# schematic.net
KiCad netlist of a schematic drawn in EasyEDA
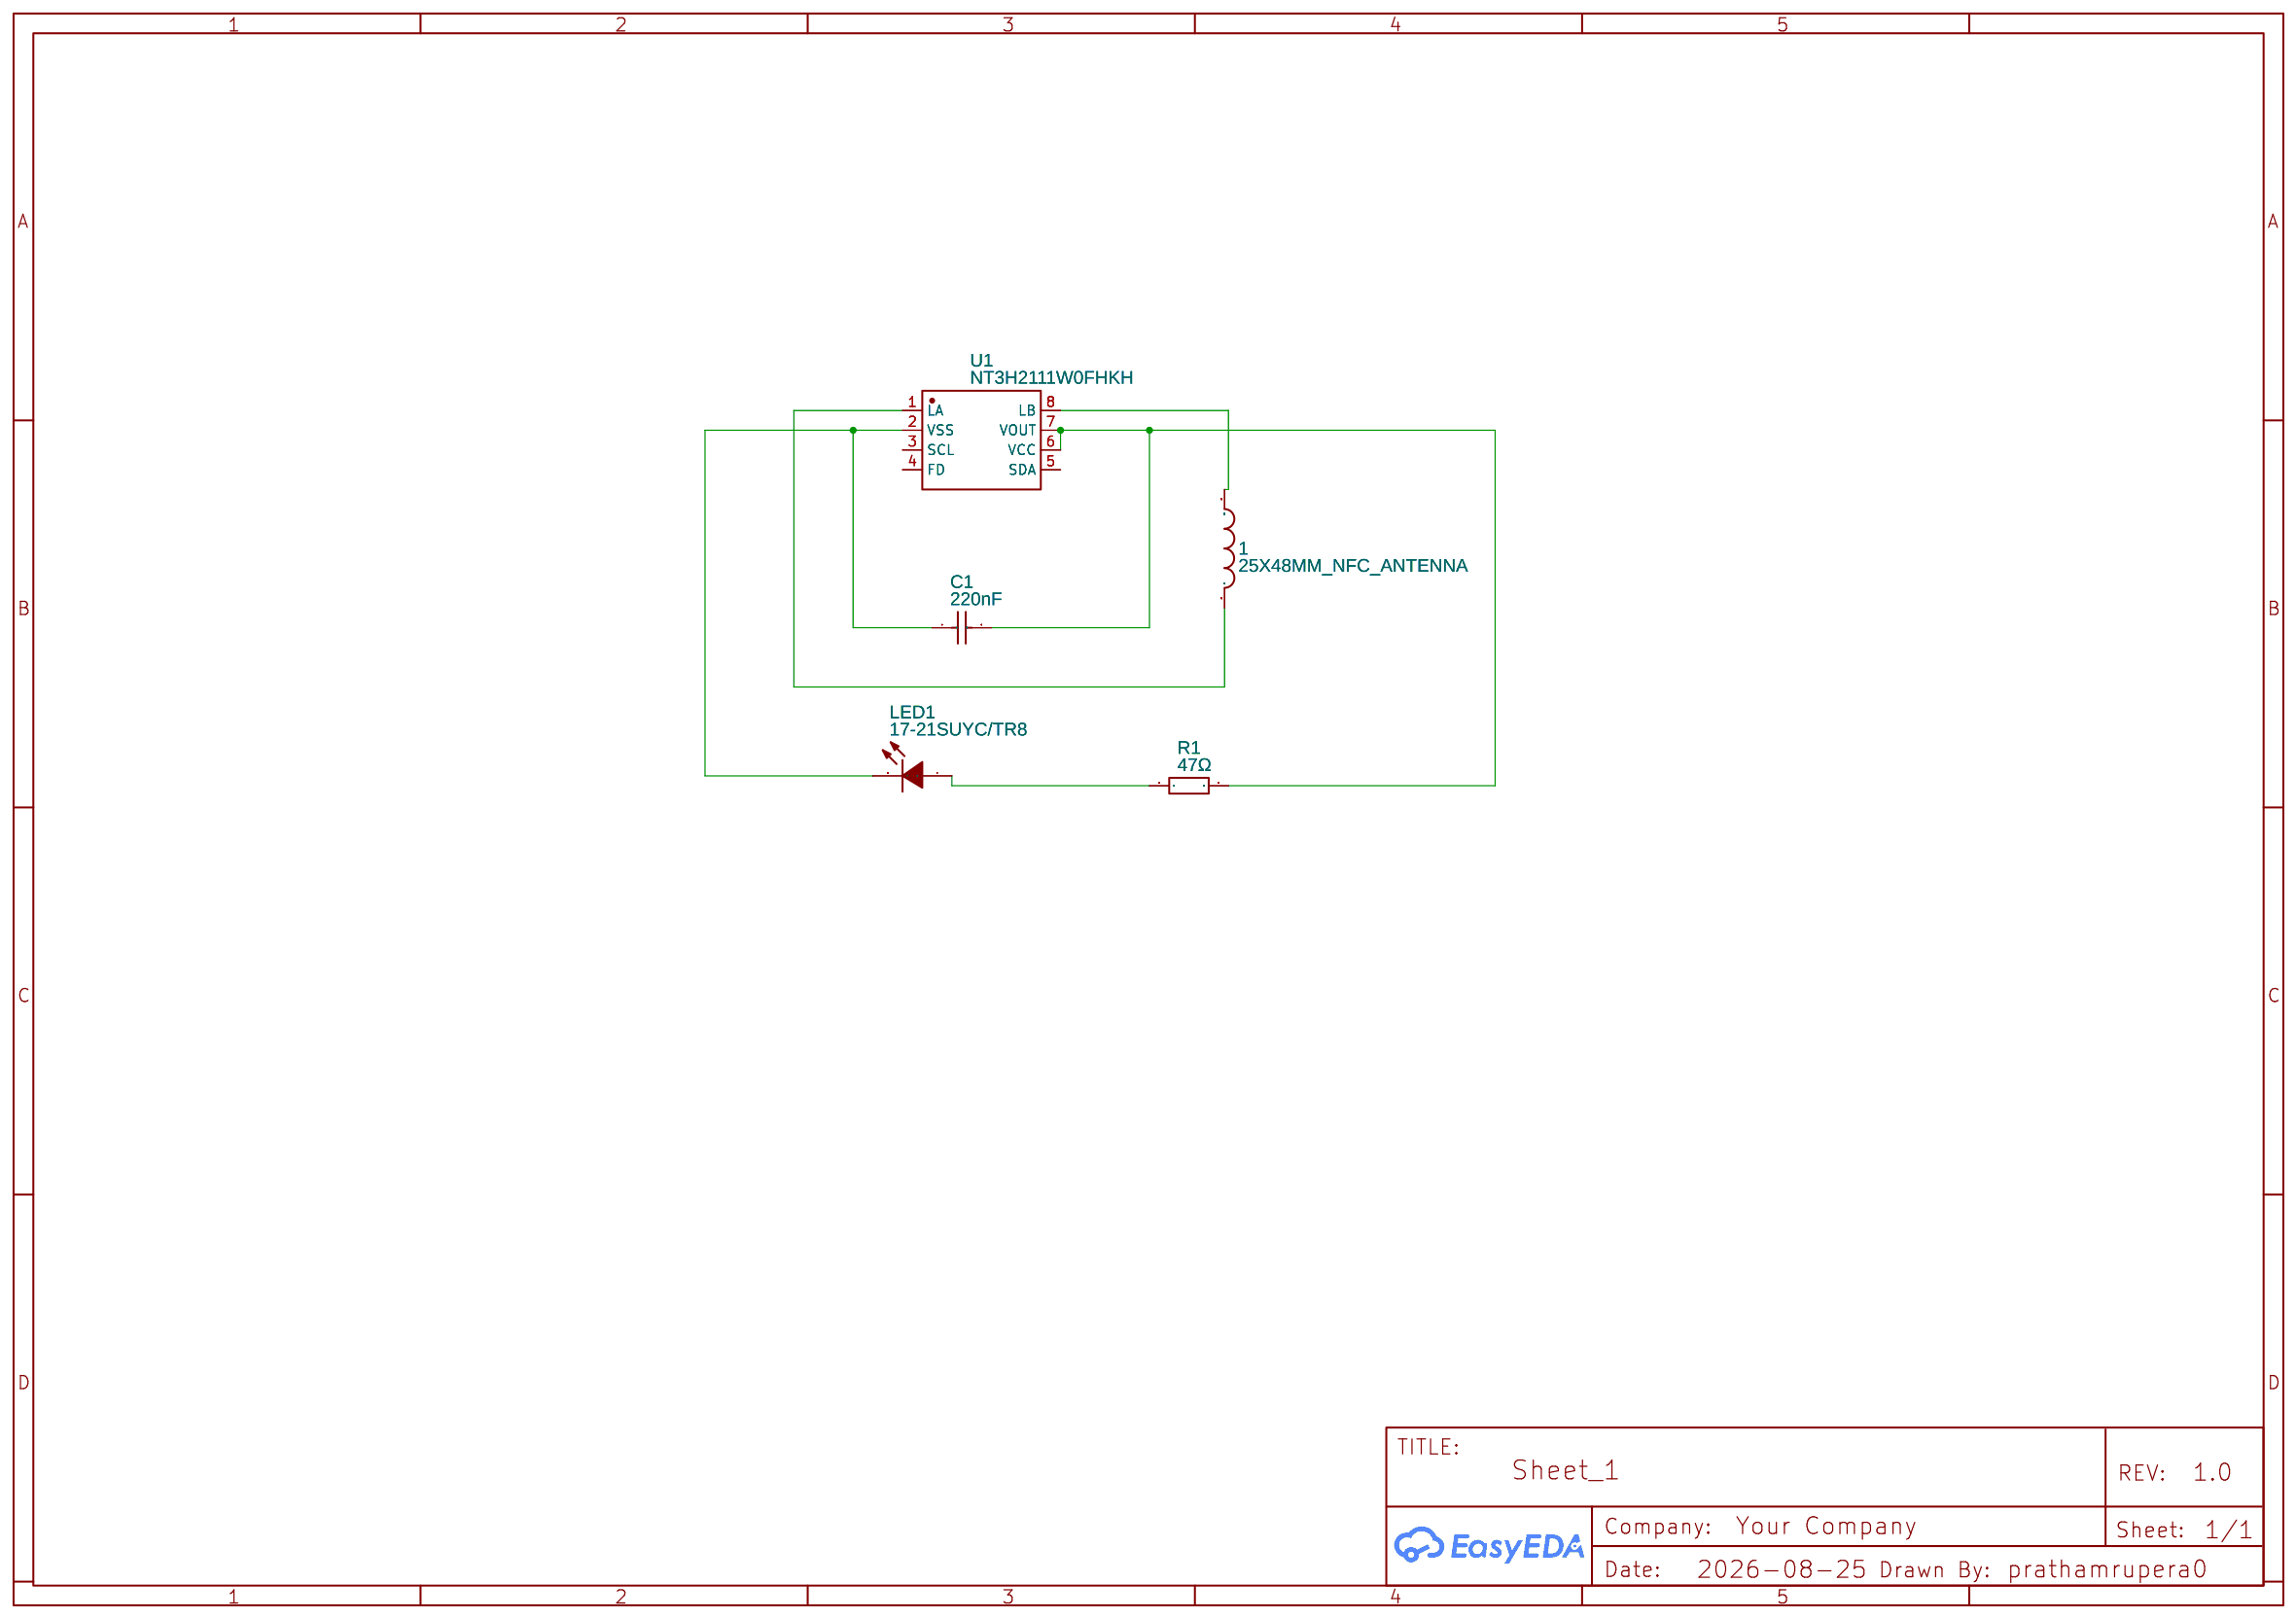
[diagram p0: schematic sheet]

(export (version "E")
  (design (tool "Eeschema 10.0.6"))
  (components
    (comp (ref "1") (value "25X48MM_NFC_ANTENNA") (libsource (lib "") (part "25X48MM_NFC_ANTENNA")))
    (comp (ref "C1")
      (value "220nF")
      (fields
        (field (name "Manufacturer Part") "CL21B224KBFNNNE")
        (field (name "Manufacturer") "SAMSUNG(三星)")
      )
      (libsource (lib "") (part "CL21B224KBFNNNE"))
    )
    (comp (ref "LED1")
      (value "17-21SUYC/TR8")
      (fields (field (name "Manufacturer Part") "KT-0805黄灯") (field (name "Manufacturer") "KENTO"))
      (libsource (lib "") (part "17-21SUYC/TR8"))
    )
    (comp (ref "R1")
      (value "47Ω")
      (fields (field (name "Manufacturer Part") "KNP2W-47Ω±5% MK型") (field (name "Manufacturer") "CCO(千志电子)"))
      (libsource (lib "") (part "47Ω(470) ±5%"))
    )
    (comp (ref "U1")
      (value "NT3H2111W0FHKH")
      (fields (field (name "Manufacturer") "NXP(恩智浦)"))
      (libsource (lib "") (part "NT3H2111W0FHKH"))
    )
  )
  (nets
    (net (code "1") (name "Net-(LED1-+)") (class "Default")
      (node (ref "LED1") (pin "1") (pinfunction "+_1") (pintype "unspecified"))
      (node (ref "R1") (pin "1") (pinfunction "1_1") (pintype "unspecified"))
    )
    (net (code "2") (name "Net-(LED1--)") (class "Default")
      (node (ref "C1") (pin "1") (pinfunction "1_1") (pintype "input"))
      (node (ref "LED1") (pin "2") (pinfunction "-_2") (pintype "unspecified"))
      (node (ref "U1") (pin "2") (pinfunction "VSS_2") (pintype "unspecified"))
    )
    (net (code "3") (name "Net-(U1-LA)") (class "Default")
      (node (ref "1") (pin "P$2") (pinfunction "P$2_P$2") (pintype "bidirectional"))
      (node (ref "U1") (pin "1") (pinfunction "LA_1") (pintype "unspecified"))
    )
    (net (code "4") (name "Net-(U1-LB)") (class "Default")
      (node (ref "1") (pin "P$1") (pinfunction "P$1_P$1") (pintype "bidirectional"))
      (node (ref "U1") (pin "8") (pinfunction "LB_8") (pintype "unspecified"))
    )
    (net (code "5") (name "Net-(U1-VCC)") (class "Default")
      (node (ref "C1") (pin "2") (pinfunction "2_2") (pintype "input"))
      (node (ref "R1") (pin "2") (pinfunction "2_2") (pintype "unspecified"))
      (node (ref "U1") (pin "6") (pinfunction "VCC_6") (pintype "unspecified"))
      (node (ref "U1") (pin "7") (pinfunction "VOUT_7") (pintype "unspecified"))
    )
    (net (code "6") (name "unconnected-(U1-FD-Pad4)") (class "Default")
      (node (ref "U1") (pin "4") (pinfunction "FD_4") (pintype "unspecified"))
    )
    (net (code "7") (name "unconnected-(U1-SCL-Pad3)") (class "Default")
      (node (ref "U1") (pin "3") (pinfunction "SCL_3") (pintype "unspecified"))
    )
    (net (code "8") (name "unconnected-(U1-SDA-Pad5)") (class "Default")
      (node (ref "U1") (pin "5") (pinfunction "SDA_5") (pintype "unspecified"))
    )
  )
)
